# mainboardv1_2.net
KiCad netlist of a schematic drawn in EAGLE
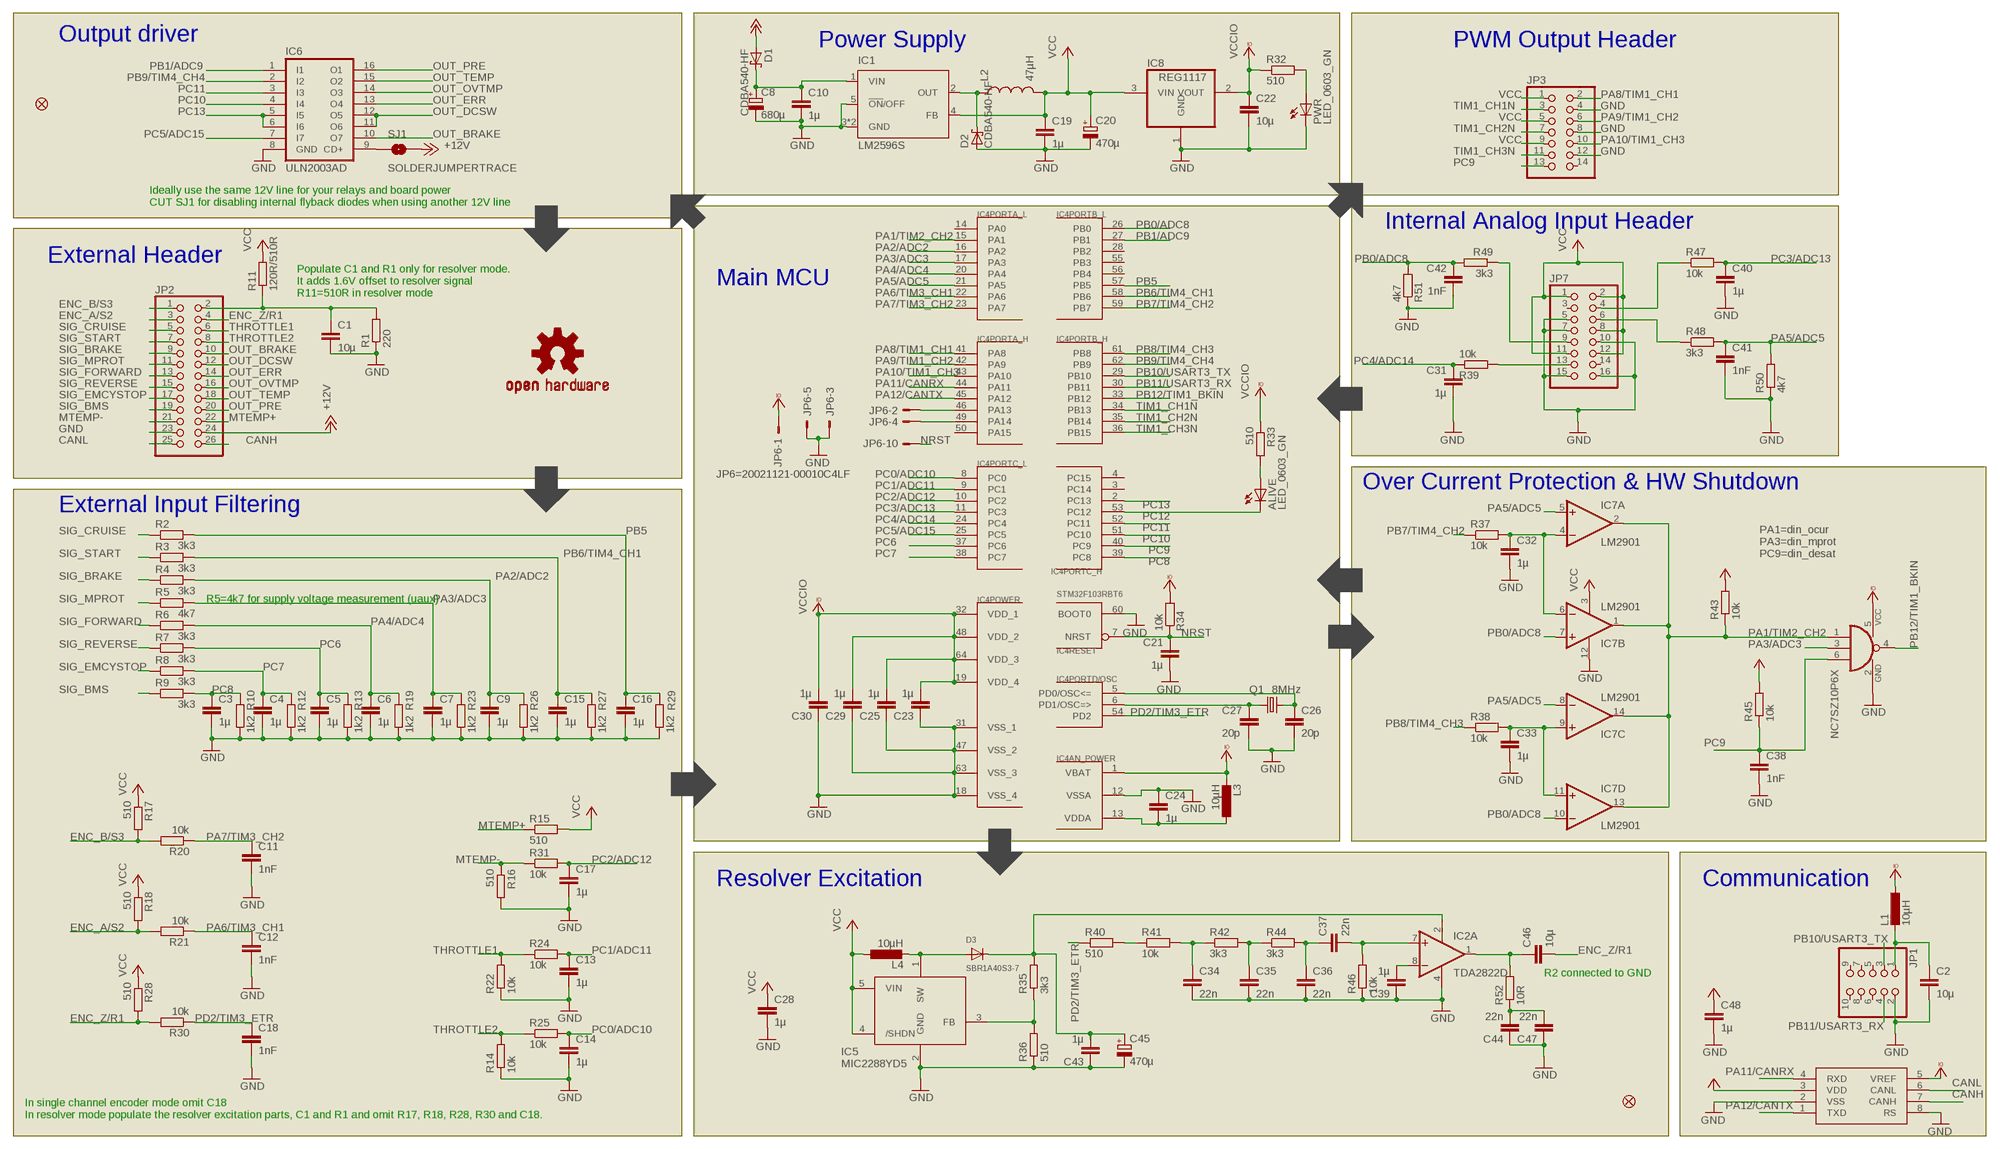
[diagram p0: schematic, sheet 1]

(export (version "E")
  (design (tool "Eeschema 10.0.6"))
  (components
    (comp (ref "ALIVE")
      (value "LED_0603_GN")
      (footprint "eagle-import:SML0805")
      (libsource (lib "eagle-import") (part "LEDSML0805"))
    )
    (comp (ref "C1")
      (value "10µ")
      (footprint "eagle-import:C0805")
      (libsource (lib "eagle-import") (part "C-EUC0805"))
    )
    (comp (ref "C2")
      (value "10µ")
      (footprint "eagle-import:C0805")
      (libsource (lib "eagle-import") (part "C-EUC0805"))
    )
    (comp (ref "C3")
      (value "1µ")
      (footprint "eagle-import:C0603")
      (libsource (lib "eagle-import") (part "C-EUC0603"))
    )
    (comp (ref "C4")
      (value "1µ")
      (footprint "eagle-import:C0603")
      (libsource (lib "eagle-import") (part "C-EUC0603"))
    )
    (comp (ref "C5")
      (value "1µ")
      (footprint "eagle-import:C0603")
      (libsource (lib "eagle-import") (part "C-EUC0603"))
    )
    (comp (ref "C6")
      (value "1µ")
      (footprint "eagle-import:C0603")
      (libsource (lib "eagle-import") (part "C-EUC0603"))
    )
    (comp (ref "C7")
      (value "1µ")
      (footprint "eagle-import:C0603")
      (libsource (lib "eagle-import") (part "C-EUC0603"))
    )
    (comp (ref "C8")
      (value "680µ")
      (footprint "eagle-import:UD-10X10_NICHICON")
      (libsource (lib "eagle-import") (part "CPOL-EUUD-10X10"))
    )
    (comp (ref "C9")
      (value "1µ")
      (footprint "eagle-import:C0603")
      (libsource (lib "eagle-import") (part "C-EUC0603"))
    )
    (comp (ref "C10")
      (value "1µ")
      (footprint "eagle-import:C0603")
      (libsource (lib "eagle-import") (part "C-EUC0603"))
    )
    (comp (ref "C11")
      (value "1nF")
      (footprint "eagle-import:C0603")
      (libsource (lib "eagle-import") (part "C-EUC0603"))
    )
    (comp (ref "C12")
      (value "1nF")
      (footprint "eagle-import:C0603")
      (libsource (lib "eagle-import") (part "C-EUC0603"))
    )
    (comp (ref "C13")
      (value "1µ")
      (footprint "eagle-import:C0603")
      (libsource (lib "eagle-import") (part "C-EUC0603"))
    )
    (comp (ref "C14")
      (value "1µ")
      (footprint "eagle-import:C0603")
      (libsource (lib "eagle-import") (part "C-EUC0603"))
    )
    (comp (ref "C15")
      (value "1µ")
      (footprint "eagle-import:C0603")
      (libsource (lib "eagle-import") (part "C-EUC0603"))
    )
    (comp (ref "C16")
      (value "1µ")
      (footprint "eagle-import:C0603")
      (libsource (lib "eagle-import") (part "C-EUC0603"))
    )
    (comp (ref "C17")
      (value "1µ")
      (footprint "eagle-import:C0603")
      (libsource (lib "eagle-import") (part "C-EUC0603"))
    )
    (comp (ref "C18")
      (value "1nF")
      (footprint "eagle-import:C0603")
      (libsource (lib "eagle-import") (part "C-EUC0603"))
    )
    (comp (ref "C19")
      (value "1µ")
      (footprint "eagle-import:C0603")
      (libsource (lib "eagle-import") (part "C-EUC0603"))
    )
    (comp (ref "C20")
      (value "470µ")
      (footprint "eagle-import:UD-6,3X7,7_NICHICON")
      (libsource (lib "eagle-import") (part "CPOL-EUUD-6,3X7,7"))
    )
    (comp (ref "C21")
      (value "1µ")
      (footprint "eagle-import:C0603")
      (libsource (lib "eagle-import") (part "C-EUC0603"))
    )
    (comp (ref "C22")
      (value "10µ")
      (footprint "eagle-import:C0805")
      (libsource (lib "eagle-import") (part "C-EUC0805"))
    )
    (comp (ref "C23")
      (value "1µ")
      (footprint "eagle-import:C0603")
      (libsource (lib "eagle-import") (part "C-EUC0603"))
    )
    (comp (ref "C24")
      (value "1µ")
      (footprint "eagle-import:C0603")
      (libsource (lib "eagle-import") (part "C-EUC0603"))
    )
    (comp (ref "C25")
      (value "1µ")
      (footprint "eagle-import:C0603")
      (libsource (lib "eagle-import") (part "C-EUC0603"))
    )
    (comp (ref "C26")
      (value "20p")
      (footprint "eagle-import:C0603")
      (libsource (lib "eagle-import") (part "C-EUC0603"))
    )
    (comp (ref "C27")
      (value "20p")
      (footprint "eagle-import:C0603")
      (libsource (lib "eagle-import") (part "C-EUC0603"))
    )
    (comp (ref "C28")
      (value "1µ")
      (footprint "eagle-import:C0603")
      (libsource (lib "eagle-import") (part "C-EUC0603"))
    )
    (comp (ref "C29")
      (value "1µ")
      (footprint "eagle-import:C0603")
      (libsource (lib "eagle-import") (part "C-EUC0603"))
    )
    (comp (ref "C30")
      (value "1µ")
      (footprint "eagle-import:C0603")
      (libsource (lib "eagle-import") (part "C-EUC0603"))
    )
    (comp (ref "C31")
      (value "1µ")
      (footprint "eagle-import:C0603")
      (libsource (lib "eagle-import") (part "C-EUC0603"))
    )
    (comp (ref "C32")
      (value "1µ")
      (footprint "eagle-import:C0603")
      (libsource (lib "eagle-import") (part "C-EUC0603"))
    )
    (comp (ref "C33")
      (value "1µ")
      (footprint "eagle-import:C0603")
      (libsource (lib "eagle-import") (part "C-EUC0603"))
    )
    (comp (ref "C34")
      (value "22n")
      (footprint "eagle-import:C0603")
      (libsource (lib "eagle-import") (part "C-EUC0603"))
    )
    (comp (ref "C35")
      (value "22n")
      (footprint "eagle-import:C0603")
      (libsource (lib "eagle-import") (part "C-EUC0603"))
    )
    (comp (ref "C36")
      (value "22n")
      (footprint "eagle-import:C0603")
      (libsource (lib "eagle-import") (part "C-EUC0603"))
    )
    (comp (ref "C37")
      (value "22n")
      (footprint "eagle-import:C0603")
      (libsource (lib "eagle-import") (part "C-EUC0603"))
    )
    (comp (ref "C38")
      (value "1nF")
      (footprint "eagle-import:C0603")
      (libsource (lib "eagle-import") (part "C-EUC0603"))
    )
    (comp (ref "C39")
      (value "1µ")
      (footprint "eagle-import:C0603")
      (libsource (lib "eagle-import") (part "C-EUC0603"))
    )
    (comp (ref "C40")
      (value "1µ")
      (footprint "eagle-import:C0603")
      (libsource (lib "eagle-import") (part "C-EUC0603"))
    )
    (comp (ref "C41")
      (value "1nF")
      (footprint "eagle-import:C0603")
      (libsource (lib "eagle-import") (part "C-EUC0603"))
    )
    (comp (ref "C42")
      (value "1nF")
      (footprint "eagle-import:C0603")
      (libsource (lib "eagle-import") (part "C-EUC0603"))
    )
    (comp (ref "C43")
      (value "1µ")
      (footprint "eagle-import:C0603")
      (libsource (lib "eagle-import") (part "C-EUC0603"))
    )
    (comp (ref "C44")
      (value "22n")
      (footprint "eagle-import:C0603")
      (libsource (lib "eagle-import") (part "C-EUC0603"))
    )
    (comp (ref "C45")
      (value "470µ")
      (footprint "eagle-import:UD-6,3X7,7_NICHICON")
      (libsource (lib "eagle-import") (part "CPOL-EUUD-6,3X7,7"))
    )
    (comp (ref "C46")
      (value "10µ")
      (footprint "eagle-import:C0805")
      (libsource (lib "eagle-import") (part "C-EUC0805"))
    )
    (comp (ref "C47")
      (value "22n")
      (footprint "eagle-import:C0603")
      (libsource (lib "eagle-import") (part "C-EUC0603"))
    )
    (comp (ref "C48")
      (value "1µ")
      (footprint "eagle-import:C0603")
      (libsource (lib "eagle-import") (part "C-EUC0603"))
    )
    (comp (ref "D1")
      (value "CDBA540-HF")
      (footprint "eagle-import:SMB")
      (libsource (lib "eagle-import") (part "SCHOTTKY-DIODESMD"))
    )
    (comp (ref "D2")
      (value "CDBA540-HF")
      (footprint "eagle-import:SMB")
      (libsource (lib "eagle-import") (part "SCHOTTKY-DIODESMD"))
    )
    (comp (ref "D3")
      (value "SBR1A40S3-7")
      (footprint "eagle-import:SOD-323F")
      (libsource (lib "eagle-import") (part "DIODESOD-323F"))
    )
    (comp (ref "FID1")
      (value "FIDUCIAL1X2.5")
      (footprint "eagle-import:FIDUCIAL-1X2.5")
      (libsource (lib "eagle-import") (part "FIDUCIAL1X2.5"))
    )
    (comp (ref "FID2")
      (value "FIDUCIAL1X2.5")
      (footprint "eagle-import:FIDUCIAL-1X2.5")
      (libsource (lib "eagle-import") (part "FIDUCIAL1X2.5"))
    )
    (comp (ref "IC1")
      (value "LM2596S")
      (footprint "eagle-import:TO263-5")
      (fields (field (name "MF") "NATIONAL SEMICONDUCTOR") (field (name "MPN") "LM2596S-ADJ/NOPB"))
      (libsource (lib "eagle-import") (part "LM2596S"))
    )
    (comp (ref "IC2")
      (value "TDA2822D")
      (footprint "eagle-import:SO08")
      (libsource (lib "eagle-import") (part "TDA2822D"))
    )
    (comp (ref "IC3")
      (value "MCP2562P")
      (footprint "eagle-import:SO08")
      (libsource (lib "eagle-import") (part "MCP2551"))
    )
    (comp (ref "IC4")
      (value "STM32F103RBT6")
      (footprint "eagle-import:TQFP64")
      (libsource (lib "eagle-import") (part "STM32F10XRXT6"))
    )
    (comp (ref "IC5")
      (value "MIC2288YD5")
      (footprint "eagle-import:SOT23-5L")
      (libsource (lib "eagle-import") (part "MIC2288YD5"))
    )
    (comp (ref "IC6")
      (value "ULN2003AD")
      (footprint "eagle-import:SO16")
      (libsource (lib "eagle-import") (part "ULN2003AD"))
    )
    (comp (ref "IC7")
      (value "LM2901")
      (footprint "eagle-import:SO14")
      (libsource (lib "eagle-import") (part "LM339D"))
    )
    (comp (ref "IC8")
      (value "REG1117")
      (footprint "eagle-import:SOT223")
      (libsource (lib "eagle-import") (part "REG1117"))
    )
    (comp (ref "IC9")
      (value "NC7SZ10P6X")
      (footprint "eagle-import:SC70-6")
      (libsource (lib "eagle-import") (part "741G10X"))
    )
    (comp (ref "JP1")
      (value "PINHD-2X5/90")
      (footprint "eagle-import:2X05_90")
      (libsource (lib "eagle-import") (part "PINHD-2X5/90"))
    )
    (comp (ref "JP2")
      (value "PINHD-2X13")
      (footprint "eagle-import:2X13")
      (libsource (lib "eagle-import") (part "PINHD-2X13"))
    )
    (comp (ref "JP3")
      (value "PINHD-2X7")
      (footprint "eagle-import:2X07")
      (libsource (lib "eagle-import") (part "PINHD-2X7"))
    )
    (comp (ref "JP6")
      (value "1365-10")
      (footprint "eagle-import:1365-10")
      (libsource (lib "eagle-import") (part "1365-10"))
    )
    (comp (ref "JP7")
      (value "PINHD-2X8")
      (footprint "eagle-import:2X08")
      (libsource (lib "eagle-import") (part "PINHD-2X8"))
    )
    (comp (ref "L1")
      (value "10µH")
      (footprint "eagle-import:L2012C")
      (libsource (lib "eagle-import") (part "L-EUL2012C"))
    )
    (comp (ref "L2")
      (value "47µH")
      (footprint "eagle-import:CDRH125")
      (libsource (lib "eagle-import") (part "INDUCTORPWR"))
    )
    (comp (ref "L3")
      (value "10µH")
      (footprint "eagle-import:L2012C")
      (libsource (lib "eagle-import") (part "L-EUL2012C"))
    )
    (comp (ref "L4")
      (value "10µH")
      (footprint "eagle-import:L2825P")
      (libsource (lib "eagle-import") (part "L-EUL2825P"))
    )
    (comp (ref "LOGO1")
      (value "OSHW-LOGOM")
      (footprint "eagle-import:OSHW-LOGO-M")
      (libsource (lib "eagle-import") (part "OSHW-LOGOM"))
    )
    (comp (ref "PWR")
      (value "LED_0603_GN")
      (footprint "eagle-import:SML0805")
      (libsource (lib "eagle-import") (part "LEDSML0805"))
    )
    (comp (ref "Q1")
      (value "8MHz")
      (footprint "eagle-import:HC49UP")
      (libsource (lib "eagle-import") (part "CRYSTALHC49UP"))
    )
    (comp (ref "R1")
      (value "220")
      (footprint "eagle-import:R0603")
      (libsource (lib "eagle-import") (part "R-EU_R0603"))
    )
    (comp (ref "R2")
      (value "3k3")
      (footprint "eagle-import:R0603")
      (libsource (lib "eagle-import") (part "R-EU_R0603"))
    )
    (comp (ref "R3")
      (value "3k3")
      (footprint "eagle-import:R0603")
      (libsource (lib "eagle-import") (part "R-EU_R0603"))
    )
    (comp (ref "R4")
      (value "3k3")
      (footprint "eagle-import:R0603")
      (libsource (lib "eagle-import") (part "R-EU_R0603"))
    )
    (comp (ref "R5")
      (value "4k7")
      (footprint "eagle-import:R0603")
      (libsource (lib "eagle-import") (part "R-EU_R0603"))
    )
    (comp (ref "R6")
      (value "3k3")
      (footprint "eagle-import:R0603")
      (libsource (lib "eagle-import") (part "R-EU_R0603"))
    )
    (comp (ref "R7")
      (value "3k3")
      (footprint "eagle-import:R0603")
      (libsource (lib "eagle-import") (part "R-EU_R0603"))
    )
    (comp (ref "R8")
      (value "3k3")
      (footprint "eagle-import:R0603")
      (libsource (lib "eagle-import") (part "R-EU_R0603"))
    )
    (comp (ref "R9")
      (value "3k3")
      (footprint "eagle-import:R0603")
      (libsource (lib "eagle-import") (part "R-EU_R0603"))
    )
    (comp (ref "R10")
      (value "1k2")
      (footprint "eagle-import:R0603")
      (libsource (lib "eagle-import") (part "R-EU_R0603"))
    )
    (comp (ref "R11")
      (value "120R/510R")
      (footprint "eagle-import:R0603")
      (libsource (lib "eagle-import") (part "R-EU_R0603"))
    )
    (comp (ref "R12")
      (value "1k2")
      (footprint "eagle-import:R0603")
      (libsource (lib "eagle-import") (part "R-EU_R0603"))
    )
    (comp (ref "R13")
      (value "1k2")
      (footprint "eagle-import:R0603")
      (libsource (lib "eagle-import") (part "R-EU_R0603"))
    )
    (comp (ref "R14")
      (value "10k")
      (footprint "eagle-import:R0603")
      (libsource (lib "eagle-import") (part "R-EU_R0603"))
    )
    (comp (ref "R15")
      (value "510")
      (footprint "eagle-import:R0603")
      (libsource (lib "eagle-import") (part "R-EU_R0603"))
    )
    (comp (ref "R16")
      (value "510")
      (footprint "eagle-import:R0603")
      (libsource (lib "eagle-import") (part "R-EU_R0603"))
    )
    (comp (ref "R17")
      (value "510")
      (footprint "eagle-import:R0603")
      (libsource (lib "eagle-import") (part "R-EU_R0603"))
    )
    (comp (ref "R18")
      (value "510")
      (footprint "eagle-import:R0603")
      (libsource (lib "eagle-import") (part "R-EU_R0603"))
    )
    (comp (ref "R19")
      (value "1k2")
      (footprint "eagle-import:R0603")
      (libsource (lib "eagle-import") (part "R-EU_R0603"))
    )
    (comp (ref "R20")
      (value "10k")
      (footprint "eagle-import:R0603")
      (libsource (lib "eagle-import") (part "R-EU_R0603"))
    )
    (comp (ref "R21")
      (value "10k")
      (footprint "eagle-import:R0603")
      (libsource (lib "eagle-import") (part "R-EU_R0603"))
    )
    (comp (ref "R22")
      (value "10k")
      (footprint "eagle-import:R0603")
      (libsource (lib "eagle-import") (part "R-EU_R0603"))
    )
    (comp (ref "R23")
      (value "1k2")
      (footprint "eagle-import:R0603")
      (libsource (lib "eagle-import") (part "R-EU_R0603"))
    )
    (comp (ref "R24")
      (value "10k")
      (footprint "eagle-import:R0603")
      (libsource (lib "eagle-import") (part "R-EU_R0603"))
    )
    (comp (ref "R25")
      (value "10k")
      (footprint "eagle-import:R0603")
      (libsource (lib "eagle-import") (part "R-EU_R0603"))
    )
    (comp (ref "R26")
      (value "1k2")
      (footprint "eagle-import:R0603")
      (libsource (lib "eagle-import") (part "R-EU_R0603"))
    )
    (comp (ref "R27")
      (value "1k2")
      (footprint "eagle-import:R0603")
      (libsource (lib "eagle-import") (part "R-EU_R0603"))
    )
    (comp (ref "R28")
      (value "510")
      (footprint "eagle-import:R0603")
      (libsource (lib "eagle-import") (part "R-EU_R0603"))
    )
    (comp (ref "R29")
      (value "1k2")
      (footprint "eagle-import:R0603")
      (libsource (lib "eagle-import") (part "R-EU_R0603"))
    )
    (comp (ref "R30")
      (value "10k")
      (footprint "eagle-import:R0603")
      (libsource (lib "eagle-import") (part "R-EU_R0603"))
    )
    (comp (ref "R31")
      (value "10k")
      (footprint "eagle-import:R0603")
      (libsource (lib "eagle-import") (part "R-EU_R0603"))
    )
    (comp (ref "R32")
      (value "510")
      (footprint "eagle-import:R0603")
      (libsource (lib "eagle-import") (part "R-EU_R0603"))
    )
    (comp (ref "R33")
      (value "510")
      (footprint "eagle-import:R0603")
      (libsource (lib "eagle-import") (part "R-EU_R0603"))
    )
    (comp (ref "R34")
      (value "10k")
      (footprint "eagle-import:R0603")
      (libsource (lib "eagle-import") (part "R-EU_R0603"))
    )
    (comp (ref "R35")
      (value "3k3")
      (footprint "eagle-import:R0603")
      (libsource (lib "eagle-import") (part "R-EU_R0603"))
    )
    (comp (ref "R36")
      (value "510")
      (footprint "eagle-import:R0603")
      (libsource (lib "eagle-import") (part "R-EU_R0603"))
    )
    (comp (ref "R37")
      (value "10k")
      (footprint "eagle-import:R0603")
      (libsource (lib "eagle-import") (part "R-EU_R0603"))
    )
    (comp (ref "R38")
      (value "10k")
      (footprint "eagle-import:R0603")
      (libsource (lib "eagle-import") (part "R-EU_R0603"))
    )
    (comp (ref "R39")
      (value "10k")
      (footprint "eagle-import:R0603")
      (libsource (lib "eagle-import") (part "R-EU_R0603"))
    )
    (comp (ref "R40")
      (value "510")
      (footprint "eagle-import:R0603")
      (libsource (lib "eagle-import") (part "R-EU_R0603"))
    )
    (comp (ref "R41")
      (value "10k")
      (footprint "eagle-import:R0603")
      (libsource (lib "eagle-import") (part "R-EU_R0603"))
    )
    (comp (ref "R42")
      (value "3k3")
      (footprint "eagle-import:R0603")
      (libsource (lib "eagle-import") (part "R-EU_R0603"))
    )
    (comp (ref "R43")
      (value "10k")
      (footprint "eagle-import:R0603")
      (libsource (lib "eagle-import") (part "R-EU_R0603"))
    )
    (comp (ref "R44")
      (value "3k3")
      (footprint "eagle-import:R0603")
      (libsource (lib "eagle-import") (part "R-EU_R0603"))
    )
    (comp (ref "R45")
      (value "10k")
      (footprint "eagle-import:R0603")
      (libsource (lib "eagle-import") (part "R-EU_R0603"))
    )
    (comp (ref "R46")
      (value "10k")
      (footprint "eagle-import:R0603")
      (libsource (lib "eagle-import") (part "R-EU_R0603"))
    )
    (comp (ref "R47")
      (value "10k")
      (footprint "eagle-import:R0603")
      (libsource (lib "eagle-import") (part "R-EU_R0603"))
    )
    (comp (ref "R48")
      (value "3k3")
      (footprint "eagle-import:R0603")
      (libsource (lib "eagle-import") (part "R-EU_R0603"))
    )
    (comp (ref "R49")
      (value "3k3")
      (footprint "eagle-import:R0603")
      (libsource (lib "eagle-import") (part "R-EU_R0603"))
    )
    (comp (ref "R50")
      (value "4k7")
      (footprint "eagle-import:R0603")
      (libsource (lib "eagle-import") (part "R-EU_R0603"))
    )
    (comp (ref "R51")
      (value "4k7")
      (footprint "eagle-import:R0603")
      (libsource (lib "eagle-import") (part "R-EU_R0603"))
    )
    (comp (ref "R52")
      (value "10R")
      (footprint "eagle-import:R0603")
      (libsource (lib "eagle-import") (part "R-EU_R0603"))
    )
    (comp (ref "SJ1")
      (value "SOLDERJUMPERTRACE")
      (footprint "eagle-import:SJ_2S-TRACE")
      (libsource (lib "eagle-import") (part "SOLDERJUMPERTRACE"))
    )
  )
  (nets
    (net (code "1") (name "+12V") (class "Default")
      (node (ref "D1") (pin "A") (pinfunction "A_A") (pintype "passive"))
      (node (ref "JP2") (pin "24") (pinfunction "24_24") (pintype "passive"))
      (node (ref "SJ1") (pin "2") (pinfunction "2_2") (pintype "passive"))
    )
    (net (code "2") (name "/CANH") (class "Default")
      (node (ref "IC3") (pin "7") (pinfunction "CANH_7") (pintype "bidirectional"))
      (node (ref "JP2") (pin "26") (pinfunction "26_26") (pintype "passive"))
    )
    (net (code "3") (name "/CANL") (class "Default")
      (node (ref "IC3") (pin "6") (pinfunction "CANL_6") (pintype "bidirectional"))
      (node (ref "JP2") (pin "25") (pinfunction "25_25") (pintype "passive"))
    )
    (net (code "4") (name "/ENC_A{slash}S2") (class "Default")
      (node (ref "JP2") (pin "3") (pinfunction "3_3") (pintype "passive"))
      (node (ref "R18") (pin "2") (pinfunction "2_2") (pintype "passive"))
      (node (ref "R21") (pin "2") (pinfunction "2_2") (pintype "passive"))
    )
    (net (code "5") (name "/ENC_B{slash}S3") (class "Default")
      (node (ref "JP2") (pin "1") (pinfunction "1_1") (pintype "passive"))
      (node (ref "R17") (pin "2") (pinfunction "2_2") (pintype "passive"))
      (node (ref "R20") (pin "2") (pinfunction "2_2") (pintype "passive"))
    )
    (net (code "6") (name "/ENC_Z{slash}R1") (class "Default")
      (node (ref "C46") (pin "2") (pinfunction "2_2") (pintype "passive"))
      (node (ref "JP2") (pin "4") (pinfunction "4_4") (pintype "passive"))
      (node (ref "R28") (pin "2") (pinfunction "2_2") (pintype "passive"))
      (node (ref "R30") (pin "2") (pinfunction "2_2") (pintype "passive"))
    )
    (net (code "7") (name "/MTEMP+") (class "Default")
      (node (ref "JP2") (pin "22") (pinfunction "22_22") (pintype "passive"))
      (node (ref "R15") (pin "1") (pinfunction "1_1") (pintype "passive"))
    )
    (net (code "8") (name "/MTEMP-") (class "Default")
      (node (ref "JP2") (pin "21") (pinfunction "21_21") (pintype "passive"))
      (node (ref "R16") (pin "1") (pinfunction "1_1") (pintype "passive"))
      (node (ref "R31") (pin "1") (pinfunction "1_1") (pintype "passive"))
    )
    (net (code "9") (name "/NRST") (class "Default")
      (node (ref "C21") (pin "1") (pinfunction "1_1") (pintype "passive"))
      (node (ref "IC4") (pin "7") (pinfunction "NRST_7") (pintype "input"))
      (node (ref "JP6") (pin "10") (pinfunction "S_10") (pintype "passive"))
      (node (ref "R34") (pin "1") (pinfunction "1_1") (pintype "passive"))
    )
    (net (code "10") (name "/OUT_BRAKE") (class "Default")
      (node (ref "IC6") (pin "10") (pinfunction "O7_10") (pintype "open_collector"))
      (node (ref "JP2") (pin "10") (pinfunction "10_10") (pintype "passive"))
    )
    (net (code "11") (name "/OUT_DCSW") (class "Default")
      (node (ref "IC6") (pin "11") (pinfunction "O6_11") (pintype "open_collector"))
      (node (ref "IC6") (pin "12") (pinfunction "O5_12") (pintype "open_collector"))
      (node (ref "JP2") (pin "12") (pinfunction "12_12") (pintype "passive"))
    )
    (net (code "12") (name "/OUT_ERR") (class "Default")
      (node (ref "IC6") (pin "13") (pinfunction "O4_13") (pintype "open_collector"))
      (node (ref "JP2") (pin "14") (pinfunction "14_14") (pintype "passive"))
    )
    (net (code "13") (name "/OUT_OVTMP") (class "Default")
      (node (ref "IC6") (pin "14") (pinfunction "O3_14") (pintype "open_collector"))
      (node (ref "JP2") (pin "16") (pinfunction "16_16") (pintype "passive"))
    )
    (net (code "14") (name "/OUT_PRE") (class "Default")
      (node (ref "IC6") (pin "16") (pinfunction "O1_16") (pintype "open_collector"))
      (node (ref "JP2") (pin "20") (pinfunction "20_20") (pintype "passive"))
    )
    (net (code "15") (name "/OUT_TEMP") (class "Default")
      (node (ref "IC6") (pin "15") (pinfunction "O2_15") (pintype "open_collector"))
      (node (ref "JP2") (pin "18") (pinfunction "18_18") (pintype "passive"))
    )
    (net (code "16") (name "/PA1{slash}TIM2_CH2") (class "Default")
      (node (ref "IC4") (pin "15") (pinfunction "PA1_15") (pintype "bidirectional"))
      (node (ref "IC7") (pin "1") (pinfunction "OUT_1") (pintype "open_collector"))
      (node (ref "IC7") (pin "13") (pinfunction "OUT_13") (pintype "open_collector"))
      (node (ref "IC7") (pin "14") (pinfunction "OUT_14") (pintype "open_collector"))
      (node (ref "IC7") (pin "2") (pinfunction "OUT_2") (pintype "open_collector"))
      (node (ref "IC9") (pin "1") (pinfunction "I0_1") (pintype "input"))
      (node (ref "R43") (pin "1") (pinfunction "1_1") (pintype "passive"))
    )
    (net (code "17") (name "/PA2{slash}ADC2") (class "Default")
      (node (ref "C9") (pin "1") (pinfunction "1_1") (pintype "passive"))
      (node (ref "IC4") (pin "16") (pinfunction "PA2_16") (pintype "bidirectional"))
      (node (ref "R26") (pin "2") (pinfunction "2_2") (pintype "passive"))
      (node (ref "R4") (pin "2") (pinfunction "2_2") (pintype "passive"))
    )
    (net (code "18") (name "/PA3{slash}ADC3") (class "Default")
      (node (ref "C7") (pin "1") (pinfunction "1_1") (pintype "passive"))
      (node (ref "IC4") (pin "17") (pinfunction "PA3_17") (pintype "bidirectional"))
      (node (ref "IC9") (pin "3") (pinfunction "I1_3") (pintype "input"))
      (node (ref "R23") (pin "2") (pinfunction "2_2") (pintype "passive"))
      (node (ref "R5") (pin "2") (pinfunction "2_2") (pintype "passive"))
    )
    (net (code "19") (name "/PA4{slash}ADC4") (class "Default")
      (node (ref "C6") (pin "1") (pinfunction "1_1") (pintype "passive"))
      (node (ref "IC4") (pin "20") (pinfunction "PA4_20") (pintype "bidirectional"))
      (node (ref "R19") (pin "2") (pinfunction "2_2") (pintype "passive"))
      (node (ref "R6") (pin "2") (pinfunction "2_2") (pintype "passive"))
    )
    (net (code "20") (name "/PA5{slash}ADC5") (class "Default")
      (node (ref "C41") (pin "1") (pinfunction "1_1") (pintype "passive"))
      (node (ref "IC4") (pin "21") (pinfunction "PA5_21") (pintype "bidirectional"))
      (node (ref "IC7") (pin "5") (pinfunction "+IN_5") (pintype "input"))
      (node (ref "IC7") (pin "8") (pinfunction "-IN_8") (pintype "input"))
      (node (ref "R48") (pin "2") (pinfunction "2_2") (pintype "passive"))
      (node (ref "R50") (pin "2") (pinfunction "2_2") (pintype "passive"))
    )
    (net (code "21") (name "/PA6{slash}TIM3_CH1") (class "Default")
      (node (ref "C12") (pin "1") (pinfunction "1_1") (pintype "passive"))
      (node (ref "IC4") (pin "22") (pinfunction "PA6_22") (pintype "bidirectional"))
      (node (ref "R21") (pin "1") (pinfunction "1_1") (pintype "passive"))
    )
    (net (code "22") (name "/PA7{slash}TIM3_CH2") (class "Default")
      (node (ref "C11") (pin "1") (pinfunction "1_1") (pintype "passive"))
      (node (ref "IC4") (pin "23") (pinfunction "PA7_23") (pintype "bidirectional"))
      (node (ref "R20") (pin "1") (pinfunction "1_1") (pintype "passive"))
    )
    (net (code "23") (name "/PA8{slash}TIM1_CH1") (class "Default")
      (node (ref "IC4") (pin "41") (pinfunction "PA8_41") (pintype "bidirectional"))
      (node (ref "JP3") (pin "2") (pinfunction "2_2") (pintype "passive"))
    )
    (net (code "24") (name "/PA9{slash}TIM1_CH2") (class "Default")
      (node (ref "IC4") (pin "42") (pinfunction "PA9_42") (pintype "bidirectional"))
      (node (ref "JP3") (pin "6") (pinfunction "6_6") (pintype "passive"))
    )
    (net (code "25") (name "/PA10{slash}TIM1_CH3") (class "Default")
      (node (ref "IC4") (pin "43") (pinfunction "PA10_43") (pintype "bidirectional"))
      (node (ref "JP3") (pin "10") (pinfunction "10_10") (pintype "passive"))
    )
    (net (code "26") (name "/PA11{slash}CANRX") (class "Default")
      (node (ref "IC3") (pin "4") (pinfunction "RXD_4") (pintype "bidirectional"))
      (node (ref "IC4") (pin "44") (pinfunction "PA11_44") (pintype "bidirectional"))
    )
    (net (code "27") (name "/PA12{slash}CANTX") (class "Default")
      (node (ref "IC3") (pin "1") (pinfunction "TXD_1") (pintype "bidirectional"))
      (node (ref "IC4") (pin "45") (pinfunction "PA12_45") (pintype "bidirectional"))
    )
    (net (code "28") (name "/PB0{slash}ADC8") (class "Default")
      (node (ref "C42") (pin "1") (pinfunction "1_1") (pintype "passive"))
      (node (ref "IC4") (pin "26") (pinfunction "PB0_26") (pintype "bidirectional"))
      (node (ref "IC7") (pin "10") (pinfunction "-IN_10") (pintype "input"))
      (node (ref "IC7") (pin "7") (pinfunction "+IN_7") (pintype "input"))
      (node (ref "R49") (pin "2") (pinfunction "2_2") (pintype "passive"))
      (node (ref "R51") (pin "2") (pinfunction "2_2") (pintype "passive"))
    )
    (net (code "29") (name "/PB1{slash}ADC9") (class "Default")
      (node (ref "IC4") (pin "27") (pinfunction "PB1_27") (pintype "bidirectional"))
      (node (ref "IC6") (pin "1") (pinfunction "I1_1") (pintype "input"))
    )
    (net (code "30") (name "/PB5") (class "Default")
      (node (ref "C16") (pin "1") (pinfunction "1_1") (pintype "passive"))
      (node (ref "IC4") (pin "57") (pinfunction "PB5_57") (pintype "bidirectional"))
      (node (ref "R2") (pin "2") (pinfunction "2_2") (pintype "passive"))
      (node (ref "R29") (pin "2") (pinfunction "2_2") (pintype "passive"))
    )
    (net (code "31") (name "/PB6{slash}TIM4_CH1") (class "Default")
      (node (ref "C15") (pin "1") (pinfunction "1_1") (pintype "passive"))
      (node (ref "IC4") (pin "58") (pinfunction "PB6_58") (pintype "bidirectional"))
      (node (ref "R27") (pin "2") (pinfunction "2_2") (pintype "passive"))
      (node (ref "R3") (pin "2") (pinfunction "2_2") (pintype "passive"))
    )
    (net (code "32") (name "/PB7{slash}TIM4_CH2") (class "Default")
      (node (ref "IC4") (pin "59") (pinfunction "PB7_59") (pintype "bidirectional"))
      (node (ref "R37") (pin "1") (pinfunction "1_1") (pintype "passive"))
    )
    (net (code "33") (name "/PB8{slash}TIM4_CH3") (class "Default")
      (node (ref "IC4") (pin "61") (pinfunction "PB8_61") (pintype "bidirectional"))
      (node (ref "R38") (pin "1") (pinfunction "1_1") (pintype "passive"))
    )
    (net (code "34") (name "/PB9{slash}TIM4_CH4") (class "Default")
      (node (ref "IC4") (pin "62") (pinfunction "PB9_62") (pintype "bidirectional"))
      (node (ref "IC6") (pin "2") (pinfunction "I2_2") (pintype "input"))
    )
    (net (code "35") (name "/PB10{slash}USART3_TX") (class "Default")
      (node (ref "IC4") (pin "29") (pinfunction "PB10_29") (pintype "bidirectional"))
      (node (ref "JP1") (pin "3") (pinfunction "3_3") (pintype "passive"))
    )
    (net (code "36") (name "/PB11{slash}USART3_RX") (class "Default")
      (node (ref "IC4") (pin "30") (pinfunction "PB11_30") (pintype "bidirectional"))
      (node (ref "JP1") (pin "4") (pinfunction "4_4") (pintype "passive"))
    )
    (net (code "37") (name "/PB12{slash}TIM1_BKIN") (class "Default")
      (node (ref "IC4") (pin "33") (pinfunction "PB12_33") (pintype "bidirectional"))
      (node (ref "IC9") (pin "4") (pinfunction "O_4") (pintype "open_collector"))
    )
    (net (code "38") (name "/PC0{slash}ADC10") (class "Default")
      (node (ref "C14") (pin "1") (pinfunction "1_1") (pintype "passive"))
      (node (ref "IC4") (pin "8") (pinfunction "PC0_8") (pintype "bidirectional"))
      (node (ref "R25") (pin "2") (pinfunction "2_2") (pintype "passive"))
    )
    (net (code "39") (name "/PC1{slash}ADC11") (class "Default")
      (node (ref "C13") (pin "1") (pinfunction "1_1") (pintype "passive"))
      (node (ref "IC4") (pin "9") (pinfunction "PC1_9") (pintype "bidirectional"))
      (node (ref "R24") (pin "2") (pinfunction "2_2") (pintype "passive"))
    )
    (net (code "40") (name "/PC2{slash}ADC12") (class "Default")
      (node (ref "C17") (pin "1") (pinfunction "1_1") (pintype "passive"))
      (node (ref "IC4") (pin "10") (pinfunction "PC2_10") (pintype "bidirectional"))
      (node (ref "R31") (pin "2") (pinfunction "2_2") (pintype "passive"))
    )
    (net (code "41") (name "/PC3{slash}ADC13") (class "Default")
      (node (ref "C40") (pin "1") (pinfunction "1_1") (pintype "passive"))
      (node (ref "IC4") (pin "11") (pinfunction "PC3_11") (pintype "bidirectional"))
      (node (ref "R47") (pin "2") (pinfunction "2_2") (pintype "passive"))
    )
    (net (code "42") (name "/PC4{slash}ADC14") (class "Default")
      (node (ref "C31") (pin "1") (pinfunction "1_1") (pintype "passive"))
      (node (ref "IC4") (pin "24") (pinfunction "PC4_24") (pintype "bidirectional"))
      (node (ref "R39") (pin "1") (pinfunction "1_1") (pintype "passive"))
    )
    (net (code "43") (name "/PC5{slash}ADC15") (class "Default")
      (node (ref "IC4") (pin "25") (pinfunction "PC5_25") (pintype "bidirectional"))
      (node (ref "IC6") (pin "7") (pinfunction "I7_7") (pintype "input"))
    )
    (net (code "44") (name "/PC6") (class "Default")
      (node (ref "C5") (pin "1") (pinfunction "1_1") (pintype "passive"))
      (node (ref "IC4") (pin "37") (pinfunction "PC6_37") (pintype "bidirectional"))
      (node (ref "R13") (pin "2") (pinfunction "2_2") (pintype "passive"))
      (node (ref "R7") (pin "2") (pinfunction "2_2") (pintype "passive"))
    )
    (net (code "45") (name "/PC7") (class "Default")
      (node (ref "C4") (pin "1") (pinfunction "1_1") (pintype "passive"))
      (node (ref "IC4") (pin "38") (pinfunction "PC7_38") (pintype "bidirectional"))
      (node (ref "R12") (pin "2") (pinfunction "2_2") (pintype "passive"))
      (node (ref "R8") (pin "2") (pinfunction "2_2") (pintype "passive"))
    )
    (net (code "46") (name "/PC8") (class "Default")
      (node (ref "C3") (pin "1") (pinfunction "1_1") (pintype "passive"))
      (node (ref "IC4") (pin "39") (pinfunction "PC8_39") (pintype "bidirectional"))
      (node (ref "R10") (pin "2") (pinfunction "2_2") (pintype "passive"))
      (node (ref "R9") (pin "2") (pinfunction "2_2") (pintype "passive"))
    )
    (net (code "47") (name "/PC9") (class "Default")
      (node (ref "C38") (pin "1") (pinfunction "1_1") (pintype "passive"))
      (node (ref "IC4") (pin "40") (pinfunction "PC9_40") (pintype "bidirectional"))
      (node (ref "IC9") (pin "6") (pinfunction "I2_6") (pintype "input"))
      (node (ref "JP3") (pin "13") (pinfunction "13_13") (pintype "passive"))
      (node (ref "R45") (pin "1") (pinfunction "1_1") (pintype "passive"))
    )
    (net (code "48") (name "/PC10") (class "Default")
      (node (ref "IC4") (pin "51") (pinfunction "PC10_51") (pintype "bidirectional"))
      (node (ref "IC6") (pin "4") (pinfunction "I4_4") (pintype "input"))
    )
    (net (code "49") (name "/PC11") (class "Default")
      (node (ref "IC4") (pin "52") (pinfunction "PC11_52") (pintype "bidirectional"))
      (node (ref "IC6") (pin "3") (pinfunction "I3_3") (pintype "input"))
    )
    (net (code "50") (name "/PC12") (class "Default")
      (node (ref "ALIVE") (pin "C") (pinfunction "C_C") (pintype "passive"))
      (node (ref "IC4") (pin "53") (pinfunction "PC12_53") (pintype "bidirectional"))
    )
    (net (code "51") (name "/PC13") (class "Default")
      (node (ref "IC4") (pin "2") (pinfunction "PC13_2") (pintype "bidirectional"))
      (node (ref "IC6") (pin "5") (pinfunction "I5_5") (pintype "input"))
      (node (ref "IC6") (pin "6") (pinfunction "I6_6") (pintype "input"))
    )
    (net (code "52") (name "/PD2{slash}TIM3_ETR") (class "Default")
      (node (ref "C18") (pin "1") (pinfunction "1_1") (pintype "passive"))
      (node (ref "IC4") (pin "54") (pinfunction "PD2_54") (pintype "bidirectional"))
      (node (ref "R30") (pin "1") (pinfunction "1_1") (pintype "passive"))
      (node (ref "R40") (pin "1") (pinfunction "1_1") (pintype "passive"))
    )
    (net (code "53") (name "/SIG_BMS") (class "Default")
      (node (ref "JP2") (pin "19") (pinfunction "19_19") (pintype "passive"))
      (node (ref "R9") (pin "1") (pinfunction "1_1") (pintype "passive"))
    )
    (net (code "54") (name "/SIG_BRAKE") (class "Default")
      (node (ref "JP2") (pin "9") (pinfunction "9_9") (pintype "passive"))
      (node (ref "R4") (pin "1") (pinfunction "1_1") (pintype "passive"))
    )
    (net (code "55") (name "/SIG_CRUISE") (class "Default")
      (node (ref "JP2") (pin "5") (pinfunction "5_5") (pintype "passive"))
      (node (ref "R2") (pin "1") (pinfunction "1_1") (pintype "passive"))
    )
    (net (code "56") (name "/SIG_EMCYSTOP") (class "Default")
      (node (ref "JP2") (pin "17") (pinfunction "17_17") (pintype "passive"))
      (node (ref "R8") (pin "1") (pinfunction "1_1") (pintype "passive"))
    )
    (net (code "57") (name "/SIG_FORWARD") (class "Default")
      (node (ref "JP2") (pin "13") (pinfunction "13_13") (pintype "passive"))
      (node (ref "R6") (pin "1") (pinfunction "1_1") (pintype "passive"))
    )
    (net (code "58") (name "/SIG_MPROT") (class "Default")
      (node (ref "JP2") (pin "11") (pinfunction "11_11") (pintype "passive"))
      (node (ref "R5") (pin "1") (pinfunction "1_1") (pintype "passive"))
    )
    (net (code "59") (name "/SIG_REVERSE") (class "Default")
      (node (ref "JP2") (pin "15") (pinfunction "15_15") (pintype "passive"))
      (node (ref "R7") (pin "1") (pinfunction "1_1") (pintype "passive"))
    )
    (net (code "60") (name "/SIG_START") (class "Default")
      (node (ref "JP2") (pin "7") (pinfunction "7_7") (pintype "passive"))
      (node (ref "R3") (pin "1") (pinfunction "1_1") (pintype "passive"))
    )
    (net (code "61") (name "/THROTTLE1") (class "Default")
      (node (ref "JP2") (pin "6") (pinfunction "6_6") (pintype "passive"))
      (node (ref "R22") (pin "2") (pinfunction "2_2") (pintype "passive"))
      (node (ref "R24") (pin "1") (pinfunction "1_1") (pintype "passive"))
    )
    (net (code "62") (name "/THROTTLE2") (class "Default")
      (node (ref "JP2") (pin "8") (pinfunction "8_8") (pintype "passive"))
      (node (ref "R14") (pin "2") (pinfunction "2_2") (pintype "passive"))
      (node (ref "R25") (pin "1") (pinfunction "1_1") (pintype "passive"))
    )
    (net (code "63") (name "/TIM1_CH1N") (class "Default")
      (node (ref "IC4") (pin "34") (pinfunction "PB13_34") (pintype "bidirectional"))
      (node (ref "JP3") (pin "3") (pinfunction "3_3") (pintype "passive"))
    )
    (net (code "64") (name "/TIM1_CH2N") (class "Default")
      (node (ref "IC4") (pin "35") (pinfunction "PB14_35") (pintype "bidirectional"))
      (node (ref "JP3") (pin "7") (pinfunction "7_7") (pintype "passive"))
    )
    (net (code "65") (name "/TIM1_CH3N") (class "Default")
      (node (ref "IC4") (pin "36") (pinfunction "PB15_36") (pintype "bidirectional"))
      (node (ref "JP3") (pin "11") (pinfunction "11_11") (pintype "passive"))
    )
    (net (code "66") (name "GND") (class "Default")
      (node (ref "C1") (pin "2") (pinfunction "2_2") (pintype "passive"))
      (node (ref "C10") (pin "2") (pinfunction "2_2") (pintype "passive"))
      (node (ref "C11") (pin "2") (pinfunction "2_2") (pintype "passive"))
      (node (ref "C12") (pin "2") (pinfunction "2_2") (pintype "passive"))
      (node (ref "C13") (pin "2") (pinfunction "2_2") (pintype "passive"))
      (node (ref "C14") (pin "2") (pinfunction "2_2") (pintype "passive"))
      (node (ref "C15") (pin "2") (pinfunction "2_2") (pintype "passive"))
      (node (ref "C16") (pin "2") (pinfunction "2_2") (pintype "passive"))
      (node (ref "C17") (pin "2") (pinfunction "2_2") (pintype "passive"))
      (node (ref "C18") (pin "2") (pinfunction "2_2") (pintype "passive"))
      (node (ref "C19") (pin "2") (pinfunction "2_2") (pintype "passive"))
      (node (ref "C2") (pin "2") (pinfunction "2_2") (pintype "passive"))
      (node (ref "C20") (pin "-") (pinfunction "-_-") (pintype "passive"))
      (node (ref "C21") (pin "2") (pinfunction "2_2") (pintype "passive"))
      (node (ref "C22") (pin "2") (pinfunction "2_2") (pintype "passive"))
      (node (ref "C23") (pin "1") (pinfunction "1_1") (pintype "passive"))
      (node (ref "C24") (pin "1") (pinfunction "1_1") (pintype "passive"))
      (node (ref "C25") (pin "1") (pinfunction "1_1") (pintype "passive"))
      (node (ref "C26") (pin "2") (pinfunction "2_2") (pintype "passive"))
      (node (ref "C27") (pin "2") (pinfunction "2_2") (pintype "passive"))
      (node (ref "C28") (pin "2") (pinfunction "2_2") (pintype "passive"))
      (node (ref "C29") (pin "1") (pinfunction "1_1") (pintype "passive"))
      (node (ref "C3") (pin "2") (pinfunction "2_2") (pintype "passive"))
      (node (ref "C30") (pin "1") (pinfunction "1_1") (pintype "passive"))
      (node (ref "C31") (pin "2") (pinfunction "2_2") (pintype "passive"))
      (node (ref "C32") (pin "2") (pinfunction "2_2") (pintype "passive"))
      (node (ref "C33") (pin "2") (pinfunction "2_2") (pintype "passive"))
      (node (ref "C34") (pin "2") (pinfunction "2_2") (pintype "passive"))
      (node (ref "C35") (pin "2") (pinfunction "2_2") (pintype "passive"))
      (node (ref "C36") (pin "2") (pinfunction "2_2") (pintype "passive"))
      (node (ref "C38") (pin "2") (pinfunction "2_2") (pintype "passive"))
      (node (ref "C39") (pin "1") (pinfunction "1_1") (pintype "passive"))
      (node (ref "C4") (pin "2") (pinfunction "2_2") (pintype "passive"))
      (node (ref "C40") (pin "2") (pinfunction "2_2") (pintype "passive"))
      (node (ref "C41") (pin "2") (pinfunction "2_2") (pintype "passive"))
      (node (ref "C42") (pin "2") (pinfunction "2_2") (pintype "passive"))
      (node (ref "C43") (pin "1") (pinfunction "1_1") (pintype "passive"))
      (node (ref "C44") (pin "1") (pinfunction "1_1") (pintype "passive"))
      (node (ref "C45") (pin "-") (pinfunction "-_-") (pintype "passive"))
      (node (ref "C47") (pin "1") (pinfunction "1_1") (pintype "passive"))
      (node (ref "C48") (pin "2") (pinfunction "2_2") (pintype "passive"))
      (node (ref "C5") (pin "2") (pinfunction "2_2") (pintype "passive"))
      (node (ref "C6") (pin "2") (pinfunction "2_2") (pintype "passive"))
      (node (ref "C7") (pin "2") (pinfunction "2_2") (pintype "passive"))
      (node (ref "C8") (pin "-") (pinfunction "-_-") (pintype "passive"))
      (node (ref "C9") (pin "2") (pinfunction "2_2") (pintype "passive"))
      (node (ref "D2") (pin "A") (pinfunction "A_A") (pintype "passive"))
      (node (ref "IC1") (pin "3") (pinfunction "GND_3") (pintype "power_in"))
      (node (ref "IC1") (pin "5") (pinfunction "~{ON}/OFF_5") (pintype "input"))
      (node (ref "IC1") (pin "6") (pinfunction "GND_6") (pintype "power_in"))
      (node (ref "IC2") (pin "4") (pinfunction "V-_4") (pintype "power_in"))
      (node (ref "IC3") (pin "2") (pinfunction "VSS_2") (pintype "bidirectional"))
      (node (ref "IC3") (pin "8") (pinfunction "RS_8") (pintype "bidirectional"))
      (node (ref "IC4") (pin "12") (pinfunction "VSSA_12") (pintype "power_in"))
      (node (ref "IC4") (pin "18") (pinfunction "VSS_4_18") (pintype "power_in"))
      (node (ref "IC4") (pin "31") (pinfunction "VSS_1_31") (pintype "power_in"))
      (node (ref "IC4") (pin "47") (pinfunction "VSS_2_47") (pintype "power_in"))
      (node (ref "IC4") (pin "60") (pinfunction "BOOT0_60") (pintype "input"))
      (node (ref "IC4") (pin "63") (pinfunction "VSS_3_63") (pintype "power_in"))
      (node (ref "IC5") (pin "2") (pinfunction "GND_2") (pintype "power_in"))
      (node (ref "IC6") (pin "8") (pinfunction "GND_8") (pintype "power_in"))
      (node (ref "IC7") (pin "12") (pinfunction "GND_12") (pintype "power_in"))
      (node (ref "IC8") (pin "1") (pinfunction "GND_1") (pintype "power_in"))
      (node (ref "IC9") (pin "2") (pinfunction "GND_2") (pintype "power_in"))
      (node (ref "JP1") (pin "2") (pinfunction "2_2") (pintype "passive"))
      (node (ref "JP2") (pin "23") (pinfunction "23_23") (pintype "passive"))
      (node (ref "JP3") (pin "12") (pinfunction "12_12") (pintype "passive"))
      (node (ref "JP3") (pin "4") (pinfunction "4_4") (pintype "passive"))
      (node (ref "JP3") (pin "8") (pinfunction "8_8") (pintype "passive"))
      (node (ref "JP6") (pin "3") (pinfunction "S_3") (pintype "passive"))
      (node (ref "JP6") (pin "5") (pinfunction "S_5") (pintype "passive"))
      (node (ref "JP7") (pin "10") (pinfunction "10_10") (pintype "passive"))
      (node (ref "JP7") (pin "15") (pinfunction "15_15") (pintype "passive"))
      (node (ref "JP7") (pin "16") (pinfunction "16_16") (pintype "passive"))
      (node (ref "JP7") (pin "5") (pinfunction "5_5") (pintype "passive"))
      (node (ref "JP7") (pin "7") (pinfunction "7_7") (pintype "passive"))
      (node (ref "PWR") (pin "C") (pinfunction "C_C") (pintype "passive"))
      (node (ref "R1") (pin "1") (pinfunction "1_1") (pintype "passive"))
      (node (ref "R10") (pin "1") (pinfunction "1_1") (pintype "passive"))
      (node (ref "R12") (pin "1") (pinfunction "1_1") (pintype "passive"))
      (node (ref "R13") (pin "1") (pinfunction "1_1") (pintype "passive"))
      (node (ref "R14") (pin "1") (pinfunction "1_1") (pintype "passive"))
      (node (ref "R16") (pin "2") (pinfunction "2_2") (pintype "passive"))
      (node (ref "R19") (pin "1") (pinfunction "1_1") (pintype "passive"))
      (node (ref "R22") (pin "1") (pinfunction "1_1") (pintype "passive"))
      (node (ref "R23") (pin "1") (pinfunction "1_1") (pintype "passive"))
      (node (ref "R26") (pin "1") (pinfunction "1_1") (pintype "passive"))
      (node (ref "R27") (pin "1") (pinfunction "1_1") (pintype "passive"))
      (node (ref "R29") (pin "1") (pinfunction "1_1") (pintype "passive"))
      (node (ref "R36") (pin "1") (pinfunction "1_1") (pintype "passive"))
      (node (ref "R46") (pin "1") (pinfunction "1_1") (pintype "passive"))
      (node (ref "R50") (pin "1") (pinfunction "1_1") (pintype "passive"))
      (node (ref "R51") (pin "1") (pinfunction "1_1") (pintype "passive"))
    )
    (net (code "67") (name "Net-(ALIVE-PadA)") (class "Default")
      (node (ref "ALIVE") (pin "A") (pinfunction "A_A") (pintype "passive"))
      (node (ref "R33") (pin "2") (pinfunction "2_2") (pintype "passive"))
    )
    (net (code "68") (name "Net-(C1-Pad1)") (class "Default")
      (node (ref "C1") (pin "1") (pinfunction "1_1") (pintype "passive"))
      (node (ref "JP2") (pin "2") (pinfunction "2_2") (pintype "passive"))
      (node (ref "R1") (pin "2") (pinfunction "2_2") (pintype "passive"))
      (node (ref "R11") (pin "1") (pinfunction "1_1") (pintype "passive"))
    )
    (net (code "69") (name "Net-(C2-Pad1)") (class "Default")
      (node (ref "C2") (pin "1") (pinfunction "1_1") (pintype "passive"))
      (node (ref "JP1") (pin "1") (pinfunction "1_1") (pintype "passive"))
      (node (ref "L1") (pin "2") (pinfunction "2_2") (pintype "passive"))
    )
    (net (code "70") (name "Net-(C34-Pad1)") (class "Default")
      (node (ref "C34") (pin "1") (pinfunction "1_1") (pintype "passive"))
      (node (ref "R41") (pin "2") (pinfunction "2_2") (pintype "passive"))
      (node (ref "R42") (pin "1") (pinfunction "1_1") (pintype "passive"))
    )
    (net (code "71") (name "Net-(C35-Pad1)") (class "Default")
      (node (ref "C35") (pin "1") (pinfunction "1_1") (pintype "passive"))
      (node (ref "R42") (pin "2") (pinfunction "2_2") (pintype "passive"))
      (node (ref "R44") (pin "1") (pinfunction "1_1") (pintype "passive"))
    )
    (net (code "72") (name "Net-(C36-Pad1)") (class "Default")
      (node (ref "C36") (pin "1") (pinfunction "1_1") (pintype "passive"))
      (node (ref "C37") (pin "1") (pinfunction "1_1") (pintype "passive"))
      (node (ref "R44") (pin "2") (pinfunction "2_2") (pintype "passive"))
    )
    (net (code "73") (name "Net-(C44-Pad2)") (class "Default")
      (node (ref "C44") (pin "2") (pinfunction "2_2") (pintype "passive"))
      (node (ref "C47") (pin "2") (pinfunction "2_2") (pintype "passive"))
      (node (ref "R52") (pin "1") (pinfunction "1_1") (pintype "passive"))
    )
    (net (code "74") (name "Net-(IC1-OUT)") (class "Default")
      (node (ref "D2") (pin "C") (pinfunction "C_C") (pintype "passive"))
      (node (ref "IC1") (pin "2") (pinfunction "OUT_2") (pintype "output"))
      (node (ref "L2") (pin "1") (pinfunction "1_1") (pintype "passive"))
    )
    (net (code "75") (name "Net-(IC1-VIN)") (class "Default")
      (node (ref "C10") (pin "1") (pinfunction "1_1") (pintype "passive"))
      (node (ref "C8") (pin "+") (pinfunction "+_+") (pintype "passive"))
      (node (ref "D1") (pin "C") (pinfunction "C_C") (pintype "passive"))
      (node (ref "IC1") (pin "1") (pinfunction "VIN_1") (pintype "input"))
    )
    (net (code "76") (name "Net-(IC2A-+IN)") (class "Default")
      (node (ref "C37") (pin "2") (pinfunction "2_2") (pintype "passive"))
      (node (ref "IC2") (pin "7") (pinfunction "+IN_7") (pintype "input"))
      (node (ref "R46") (pin "2") (pinfunction "2_2") (pintype "passive"))
    )
    (net (code "77") (name "Net-(IC2A--IN)") (class "Default")
      (node (ref "C39") (pin "2") (pinfunction "2_2") (pintype "passive"))
      (node (ref "IC2") (pin "8") (pinfunction "-IN_8") (pintype "input"))
    )
    (net (code "78") (name "Net-(IC2A-OUT)") (class "Default")
      (node (ref "C46") (pin "1") (pinfunction "1_1") (pintype "passive"))
      (node (ref "IC2") (pin "1") (pinfunction "OUT_1") (pintype "output"))
      (node (ref "R52") (pin "2") (pinfunction "2_2") (pintype "passive"))
    )
    (net (code "79") (name "Net-(IC2C-V+)") (class "Default")
      (node (ref "C43") (pin "2") (pinfunction "2_2") (pintype "passive"))
      (node (ref "C45") (pin "+") (pinfunction "+_+") (pintype "passive"))
      (node (ref "D3") (pin "C") (pinfunction "C_C") (pintype "passive"))
      (node (ref "IC2") (pin "2") (pinfunction "V+_2") (pintype "power_in"))
      (node (ref "R35") (pin "2") (pinfunction "2_2") (pintype "passive"))
    )
    (net (code "80") (name "Net-(IC4A-VDDA)") (class "Default")
      (node (ref "C24") (pin "2") (pinfunction "2_2") (pintype "passive"))
      (node (ref "IC4") (pin "13") (pinfunction "VDDA_13") (pintype "power_in"))
      (node (ref "L3") (pin "1") (pinfunction "1_1") (pintype "passive"))
    )
    (net (code "81") (name "Net-(IC4B-PA13)") (class "Default")
      (node (ref "IC4") (pin "46") (pinfunction "PA13_46") (pintype "bidirectional"))
      (node (ref "JP6") (pin "2") (pinfunction "S_2") (pintype "passive"))
    )
    (net (code "82") (name "Net-(IC4B-PA14)") (class "Default")
      (node (ref "IC4") (pin "49") (pinfunction "PA14_49") (pintype "bidirectional"))
      (node (ref "JP6") (pin "4") (pinfunction "S_4") (pintype "passive"))
    )
    (net (code "83") (name "Net-(IC4H-PD0{slash}OSC<=)") (class "Default")
      (node (ref "C26") (pin "1") (pinfunction "1_1") (pintype "passive"))
      (node (ref "IC4") (pin "5") (pinfunction "PD0/OSC<=_5") (pintype "bidirectional"))
      (node (ref "Q1") (pin "2") (pinfunction "2_2") (pintype "passive"))
    )
    (net (code "84") (name "Net-(IC4H-PD1{slash}OSC=>)") (class "Default")
      (node (ref "C27") (pin "1") (pinfunction "1_1") (pintype "passive"))
      (node (ref "IC4") (pin "6") (pinfunction "PD1/OSC=>_6") (pintype "bidirectional"))
      (node (ref "Q1") (pin "1") (pinfunction "1_1") (pintype "passive"))
    )
    (net (code "85") (name "Net-(IC5-FB)") (class "Default")
      (node (ref "IC5") (pin "3") (pinfunction "FB_3") (pintype "input"))
      (node (ref "R35") (pin "1") (pinfunction "1_1") (pintype "passive"))
      (node (ref "R36") (pin "2") (pinfunction "2_2") (pintype "passive"))
    )
    (net (code "86") (name "Net-(IC5-SW)") (class "Default")
      (node (ref "D3") (pin "A") (pinfunction "A_A") (pintype "passive"))
      (node (ref "IC5") (pin "1") (pinfunction "SW_1") (pintype "output"))
      (node (ref "L4") (pin "2") (pinfunction "2_2") (pintype "passive"))
    )
    (net (code "87") (name "Net-(IC6-CD+)") (class "Default")
      (node (ref "IC6") (pin "9") (pinfunction "CD+_9") (pintype "passive"))
      (node (ref "SJ1") (pin "1") (pinfunction "1_1") (pintype "passive"))
    )
    (net (code "88") (name "Net-(IC7A--IN)") (class "Default")
      (node (ref "C32") (pin "1") (pinfunction "1_1") (pintype "passive"))
      (node (ref "IC7") (pin "4") (pinfunction "-IN_4") (pintype "input"))
      (node (ref "IC7") (pin "6") (pinfunction "-IN_6") (pintype "input"))
      (node (ref "R37") (pin "2") (pinfunction "2_2") (pintype "passive"))
    )
    (net (code "89") (name "Net-(IC7C-+IN)") (class "Default")
      (node (ref "C33") (pin "1") (pinfunction "1_1") (pintype "passive"))
      (node (ref "IC7") (pin "11") (pinfunction "+IN_11") (pintype "input"))
      (node (ref "IC7") (pin "9") (pinfunction "+IN_9") (pintype "input"))
      (node (ref "R38") (pin "2") (pinfunction "2_2") (pintype "passive"))
    )
    (net (code "90") (name "Net-(JP7-Pad4)") (class "Default")
      (node (ref "JP7") (pin "4") (pinfunction "4_4") (pintype "passive"))
      (node (ref "R47") (pin "1") (pinfunction "1_1") (pintype "passive"))
    )
    (net (code "91") (name "Net-(JP7-Pad6)") (class "Default")
      (node (ref "JP7") (pin "6") (pinfunction "6_6") (pintype "passive"))
      (node (ref "R48") (pin "1") (pinfunction "1_1") (pintype "passive"))
    )
    (net (code "92") (name "Net-(JP7-Pad9)") (class "Default")
      (node (ref "JP7") (pin "9") (pinfunction "9_9") (pintype "passive"))
      (node (ref "R49") (pin "1") (pinfunction "1_1") (pintype "passive"))
    )
    (net (code "93") (name "Net-(JP7-Pad13)") (class "Default")
      (node (ref "JP7") (pin "13") (pinfunction "13_13") (pintype "passive"))
      (node (ref "R39") (pin "2") (pinfunction "2_2") (pintype "passive"))
    )
    (net (code "94") (name "Net-(PWR-PadA)") (class "Default")
      (node (ref "PWR") (pin "A") (pinfunction "A_A") (pintype "passive"))
      (node (ref "R32") (pin "2") (pinfunction "2_2") (pintype "passive"))
    )
    (net (code "95") (name "Net-(R40-Pad2)") (class "Default")
      (node (ref "R40") (pin "2") (pinfunction "2_2") (pintype "passive"))
      (node (ref "R41") (pin "1") (pinfunction "1_1") (pintype "passive"))
    )
    (net (code "96") (name "VCC") (class "Default")
      (node (ref "C19") (pin "1") (pinfunction "1_1") (pintype "passive"))
      (node (ref "C20") (pin "+") (pinfunction "+_+") (pintype "passive"))
      (node (ref "C28") (pin "1") (pinfunction "1_1") (pintype "passive"))
      (node (ref "C48") (pin "1") (pinfunction "1_1") (pintype "passive"))
      (node (ref "IC1") (pin "4") (pinfunction "FB_4") (pintype "input"))
      (node (ref "IC3") (pin "3") (pinfunction "VDD_3") (pintype "bidirectional"))
      (node (ref "IC5") (pin "4") (pinfunction "/SHDN_4") (pintype "input"))
      (node (ref "IC5") (pin "5") (pinfunction "VIN_5") (pintype "input"))
      (node (ref "IC7") (pin "3") (pinfunction "V+_3") (pintype "power_in"))
      (node (ref "IC8") (pin "3") (pinfunction "VIN_3") (pintype "input"))
      (node (ref "JP3") (pin "1") (pinfunction "1_1") (pintype "passive"))
      (node (ref "JP3") (pin "5") (pinfunction "5_5") (pintype "passive"))
      (node (ref "JP3") (pin "9") (pinfunction "9_9") (pintype "passive"))
      (node (ref "JP7") (pin "1") (pinfunction "1_1") (pintype "passive"))
      (node (ref "JP7") (pin "11") (pinfunction "11_11") (pintype "passive"))
      (node (ref "JP7") (pin "12") (pinfunction "12_12") (pintype "passive"))
      (node (ref "JP7") (pin "2") (pinfunction "2_2") (pintype "passive"))
      (node (ref "JP7") (pin "8") (pinfunction "8_8") (pintype "passive"))
      (node (ref "L2") (pin "2") (pinfunction "2_2") (pintype "passive"))
      (node (ref "L4") (pin "1") (pinfunction "1_1") (pintype "passive"))
      (node (ref "R11") (pin "2") (pinfunction "2_2") (pintype "passive"))
      (node (ref "R15") (pin "2") (pinfunction "2_2") (pintype "passive"))
      (node (ref "R17") (pin "1") (pinfunction "1_1") (pintype "passive"))
      (node (ref "R18") (pin "1") (pinfunction "1_1") (pintype "passive"))
      (node (ref "R28") (pin "1") (pinfunction "1_1") (pintype "passive"))
      (node (ref "R43") (pin "2") (pinfunction "2_2") (pintype "passive"))
      (node (ref "R45") (pin "2") (pinfunction "2_2") (pintype "passive"))
    )
    (net (code "97") (name "VCCIO") (class "Default")
      (node (ref "C22") (pin "1") (pinfunction "1_1") (pintype "passive"))
      (node (ref "C23") (pin "2") (pinfunction "2_2") (pintype "passive"))
      (node (ref "C25") (pin "2") (pinfunction "2_2") (pintype "passive"))
      (node (ref "C29") (pin "2") (pinfunction "2_2") (pintype "passive"))
      (node (ref "C30") (pin "2") (pinfunction "2_2") (pintype "passive"))
      (node (ref "IC3") (pin "5") (pinfunction "VREF_5") (pintype "bidirectional"))
      (node (ref "IC4") (pin "1") (pinfunction "VBAT_1") (pintype "power_in"))
      (node (ref "IC4") (pin "19") (pinfunction "VDD_4_19") (pintype "power_in"))
      (node (ref "IC4") (pin "32") (pinfunction "VDD_1_32") (pintype "power_in"))
      (node (ref "IC4") (pin "48") (pinfunction "VDD_2_48") (pintype "power_in"))
      (node (ref "IC4") (pin "64") (pinfunction "VDD_3_64") (pintype "power_in"))
      (node (ref "IC8") (pin "2") (pinfunction "VOUT_2") (pintype "output"))
      (node (ref "IC9") (pin "5") (pinfunction "VCC_5") (pintype "power_in"))
      (node (ref "JP6") (pin "1") (pinfunction "S_1") (pintype "passive"))
      (node (ref "L1") (pin "1") (pinfunction "1_1") (pintype "passive"))
      (node (ref "L3") (pin "2") (pinfunction "2_2") (pintype "passive"))
      (node (ref "R32") (pin "1") (pinfunction "1_1") (pintype "passive"))
      (node (ref "R33") (pin "1") (pinfunction "1_1") (pintype "passive"))
      (node (ref "R34") (pin "2") (pinfunction "2_2") (pintype "passive"))
    )
    (net (code "98") (name "unconnected-(IC4B-PA15-Pad50)") (class "Default")
      (node (ref "IC4") (pin "50") (pinfunction "PA15_50") (pintype "bidirectional"))
    )
    (net (code "99") (name "unconnected-(IC4C-PA0-Pad14)") (class "Default")
      (node (ref "IC4") (pin "14") (pinfunction "PA0_14") (pintype "bidirectional"))
    )
    (net (code "100") (name "unconnected-(IC4E-PB2-Pad28)") (class "Default")
      (node (ref "IC4") (pin "28") (pinfunction "PB2_28") (pintype "bidirectional"))
    )
    (net (code "101") (name "unconnected-(IC4E-PB3-Pad55)") (class "Default")
      (node (ref "IC4") (pin "55") (pinfunction "PB3_55") (pintype "bidirectional"))
    )
    (net (code "102") (name "unconnected-(IC4E-PB4-Pad56)") (class "Default")
      (node (ref "IC4") (pin "56") (pinfunction "PB4_56") (pintype "bidirectional"))
    )
    (net (code "103") (name "unconnected-(IC4F-PC14-Pad3)") (class "Default")
      (node (ref "IC4") (pin "3") (pinfunction "PC14_3") (pintype "bidirectional"))
    )
    (net (code "104") (name "unconnected-(IC4F-PC15-Pad4)") (class "Default")
      (node (ref "IC4") (pin "4") (pinfunction "PC15_4") (pintype "bidirectional"))
    )
    (net (code "105") (name "unconnected-(JP1-Pad5)") (class "Default")
      (node (ref "JP1") (pin "5") (pinfunction "5_5") (pintype "passive"))
    )
    (net (code "106") (name "unconnected-(JP1-Pad6)") (class "Default")
      (node (ref "JP1") (pin "6") (pinfunction "6_6") (pintype "passive"))
    )
    (net (code "107") (name "unconnected-(JP1-Pad7)") (class "Default")
      (node (ref "JP1") (pin "7") (pinfunction "7_7") (pintype "passive"))
    )
    (net (code "108") (name "unconnected-(JP1-Pad8)") (class "Default")
      (node (ref "JP1") (pin "8") (pinfunction "8_8") (pintype "passive"))
    )
    (net (code "109") (name "unconnected-(JP1-Pad9)") (class "Default")
      (node (ref "JP1") (pin "9") (pinfunction "9_9") (pintype "passive"))
    )
    (net (code "110") (name "unconnected-(JP1-Pad10)") (class "Default")
      (node (ref "JP1") (pin "10") (pinfunction "10_10") (pintype "passive"))
    )
    (net (code "111") (name "unconnected-(JP3-Pad14)") (class "Default")
      (node (ref "JP3") (pin "14") (pinfunction "14_14") (pintype "passive"))
    )
    (net (code "112") (name "unconnected-(JP7-Pad3)") (class "Default")
      (node (ref "JP7") (pin "3") (pinfunction "3_3") (pintype "passive"))
    )
    (net (code "113") (name "unconnected-(JP7-Pad14)") (class "Default")
      (node (ref "JP7") (pin "14") (pinfunction "14_14") (pintype "passive"))
    )
  )
)
